# source_eagle.net
KiCad netlist of a schematic drawn in EAGLE
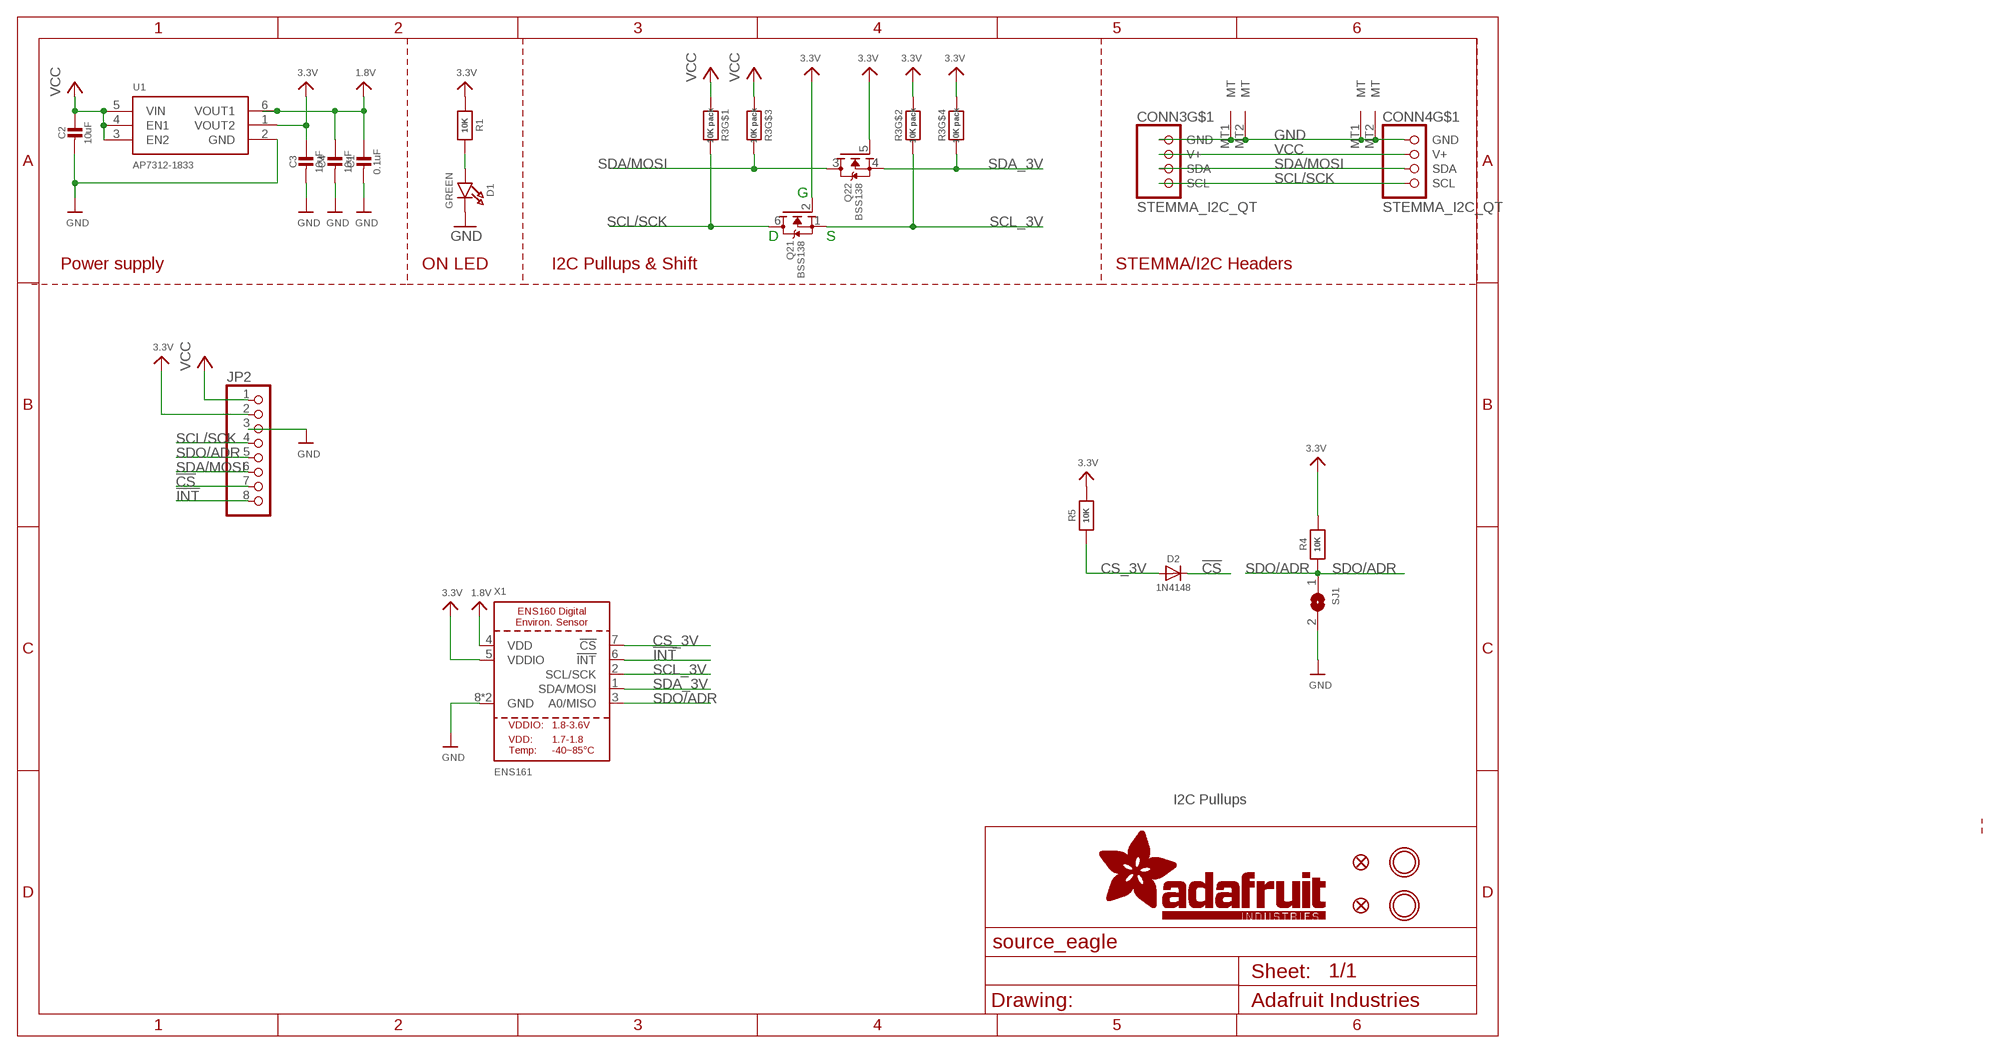
[diagram p0: schematic, sheet 1]

(export (version "E")
  (design (tool "Eeschema 10.0.6"))
  (components
    (comp (ref "C1")
      (value "0.1uF")
      (footprint "eagle-import:0603-NO")
      (libsource (lib "eagle-import") (part "CAP_CERAMIC0603_NO"))
    )
    (comp (ref "C2")
      (value "10uF")
      (footprint "eagle-import:0805-NO")
      (libsource (lib "eagle-import") (part "CAP_CERAMIC0805-NOOUTLINE"))
    )
    (comp (ref "C3")
      (value "10uF")
      (footprint "eagle-import:0805-NO")
      (libsource (lib "eagle-import") (part "CAP_CERAMIC0805-NOOUTLINE"))
    )
    (comp (ref "C4")
      (value "10uF")
      (footprint "eagle-import:0805-NO")
      (libsource (lib "eagle-import") (part "CAP_CERAMIC0805-NOOUTLINE"))
    )
    (comp (ref "CONN3")
      (value "STEMMA_I2C_QT")
      (footprint "eagle-import:JST_SH4")
      (libsource (lib "eagle-import") (part "STEMMA_I2C_QT"))
    )
    (comp (ref "CONN4")
      (value "STEMMA_I2C_QT")
      (footprint "eagle-import:JST_SH4")
      (libsource (lib "eagle-import") (part "STEMMA_I2C_QT"))
    )
    (comp (ref "D1")
      (value "GREEN")
      (footprint "eagle-import:CHIPLED_0603_NOOUTLINE")
      (libsource (lib "eagle-import") (part "LED0603_NOOUTLINE"))
    )
    (comp (ref "D2")
      (value "1N4148")
      (footprint "eagle-import:SOD-323")
      (libsource (lib "eagle-import") (part "DIODESOD-323"))
    )
    (comp (ref "FID3")
      (value "FIDUCIAL_0.5MM")
      (footprint "eagle-import:FIDUCIAL_0.5MM")
      (libsource (lib "eagle-import") (part "FIDUCIAL_0.5MM"))
    )
    (comp (ref "FID4")
      (value "FIDUCIAL_0.5MM")
      (footprint "eagle-import:FIDUCIAL_0.5MM")
      (libsource (lib "eagle-import") (part "FIDUCIAL_0.5MM"))
    )
    (comp (ref "JP2")
      (value "HEADER-1X870MIL")
      (footprint "eagle-import:1X08_ROUND_70")
      (libsource (lib "eagle-import") (part "HEADER-1X870MIL"))
    )
    (comp (ref "Q2")
      (value "BSS138")
      (footprint "eagle-import:SOT363")
      (libsource (lib "eagle-import") (part "MOSFET-N_DUAL"))
    )
    (comp (ref "R1")
      (value "10K")
      (footprint "eagle-import:0603-NO")
      (libsource (lib "eagle-import") (part "RESISTOR_0603_NOOUT"))
    )
    (comp (ref "R3")
      (value "10K pack")
      (footprint "eagle-import:RESPACK_4X0603")
      (libsource (lib "eagle-import") (part "RESISTOR_4PACK"))
    )
    (comp (ref "R4")
      (value "10K")
      (footprint "eagle-import:0603-NO")
      (libsource (lib "eagle-import") (part "RESISTOR_0603_NOOUT"))
    )
    (comp (ref "R5")
      (value "10K")
      (footprint "eagle-import:0603-NO")
      (libsource (lib "eagle-import") (part "RESISTOR_0603_NOOUT"))
    )
    (comp (ref "SJ1")
      (value "SOLDERJUMPER")
      (footprint "eagle-import:SOLDERJUMPER_ARROW_NOPASTE")
      (libsource (lib "eagle-import") (part "SOLDERJUMPER"))
    )
    (comp (ref "U$1")
      (value "MOUNTINGHOLE2.5")
      (footprint "eagle-import:MOUNTINGHOLE_2.5_PLATED")
      (libsource (lib "eagle-import") (part "MOUNTINGHOLE2.5"))
    )
    (comp (ref "U$17")
      (value "MOUNTINGHOLE2.5")
      (footprint "eagle-import:MOUNTINGHOLE_2.5_PLATED")
      (libsource (lib "eagle-import") (part "MOUNTINGHOLE2.5"))
    )
    (comp (ref "U1")
      (value "AP7312-1833")
      (footprint "eagle-import:SOT23-6")
      (libsource (lib "eagle-import") (part "VREG_SOT23-6_DUALAP7312"))
    )
    (comp (ref "X1")
      (value "ENS161")
      (footprint "eagle-import:ENS160")
      (libsource (lib "eagle-import") (part "ENS160"))
    )
  )
  (nets
    (net (code "1") (name "/CS_3V") (class "Default")
      (node (ref "D2") (pin "A") (pinfunction "A_A") (pintype "passive"))
      (node (ref "R5") (pin "1") (pinfunction "1_1") (pintype "passive"))
      (node (ref "X1") (pin "7") (pinfunction "~{CS}_7") (pintype "input"))
    )
    (net (code "2") (name "/SCL_3V") (class "Default")
      (node (ref "Q2") (pin "1") (pinfunction "S_1") (pintype "bidirectional"))
      (node (ref "R3") (pin "7") (pinfunction "2_7") (pintype "passive"))
      (node (ref "X1") (pin "2") (pinfunction "SCL/SCK_2") (pintype "input"))
    )
    (net (code "3") (name "/SCL{slash}SCK") (class "Default")
      (node (ref "CONN3") (pin "4") (pinfunction "SCL_4") (pintype "passive"))
      (node (ref "CONN4") (pin "4") (pinfunction "SCL_4") (pintype "passive"))
      (node (ref "JP2") (pin "4") (pinfunction "4_4") (pintype "passive"))
      (node (ref "Q2") (pin "6") (pinfunction "D_6") (pintype "bidirectional"))
      (node (ref "R3") (pin "8") (pinfunction "2_8") (pintype "passive"))
    )
    (net (code "4") (name "/SDA_3V") (class "Default")
      (node (ref "Q2") (pin "4") (pinfunction "S_4") (pintype "bidirectional"))
      (node (ref "R3") (pin "5") (pinfunction "2_5") (pintype "passive"))
      (node (ref "X1") (pin "1") (pinfunction "SDA/MOSI_1") (pintype "input"))
    )
    (net (code "5") (name "/SDA{slash}MOSI") (class "Default")
      (node (ref "CONN3") (pin "3") (pinfunction "SDA_3") (pintype "passive"))
      (node (ref "CONN4") (pin "3") (pinfunction "SDA_3") (pintype "passive"))
      (node (ref "JP2") (pin "6") (pinfunction "6_6") (pintype "passive"))
      (node (ref "Q2") (pin "3") (pinfunction "D_3") (pintype "bidirectional"))
      (node (ref "R3") (pin "6") (pinfunction "2_6") (pintype "passive"))
    )
    (net (code "6") (name "/SDO{slash}ADR") (class "Default")
      (node (ref "JP2") (pin "5") (pinfunction "5_5") (pintype "passive"))
      (node (ref "R4") (pin "1") (pinfunction "1_1") (pintype "passive"))
      (node (ref "SJ1") (pin "1") (pinfunction "1_1") (pintype "passive"))
      (node (ref "X1") (pin "3") (pinfunction "A0/MISO_3") (pintype "output"))
    )
    (net (code "7") (name "/~{CS}") (class "Default")
      (node (ref "D2") (pin "C") (pinfunction "C_C") (pintype "passive"))
      (node (ref "JP2") (pin "7") (pinfunction "7_7") (pintype "passive"))
    )
    (net (code "8") (name "/~{INT}") (class "Default")
      (node (ref "JP2") (pin "8") (pinfunction "8_8") (pintype "passive"))
      (node (ref "X1") (pin "6") (pinfunction "~{INT}_6") (pintype "output"))
    )
    (net (code "9") (name "1.8V") (class "Default")
      (node (ref "C1") (pin "1") (pinfunction "1_1") (pintype "passive"))
      (node (ref "C4") (pin "1") (pinfunction "1_1") (pintype "passive"))
      (node (ref "U1") (pin "6") (pinfunction "VOUT1_6") (pintype "bidirectional"))
      (node (ref "X1") (pin "4") (pinfunction "VDD_4") (pintype "power_in"))
    )
    (net (code "10") (name "3.3V") (class "Default")
      (node (ref "C3") (pin "1") (pinfunction "1_1") (pintype "passive"))
      (node (ref "JP2") (pin "2") (pinfunction "2_2") (pintype "passive"))
      (node (ref "Q2") (pin "2") (pinfunction "G_2") (pintype "bidirectional"))
      (node (ref "Q2") (pin "5") (pinfunction "G_5") (pintype "bidirectional"))
      (node (ref "R1") (pin "1") (pinfunction "1_1") (pintype "passive"))
      (node (ref "R3") (pin "2") (pinfunction "1_2") (pintype "passive"))
      (node (ref "R3") (pin "4") (pinfunction "1_4") (pintype "passive"))
      (node (ref "R4") (pin "2") (pinfunction "2_2") (pintype "passive"))
      (node (ref "R5") (pin "2") (pinfunction "2_2") (pintype "passive"))
      (node (ref "U1") (pin "1") (pinfunction "VOUT2_1") (pintype "bidirectional"))
      (node (ref "X1") (pin "5") (pinfunction "VDDIO_5") (pintype "power_in"))
    )
    (net (code "11") (name "GND") (class "Default")
      (node (ref "C1") (pin "2") (pinfunction "2_2") (pintype "passive"))
      (node (ref "C2") (pin "2") (pinfunction "2_2") (pintype "passive"))
      (node (ref "C3") (pin "2") (pinfunction "2_2") (pintype "passive"))
      (node (ref "C4") (pin "2") (pinfunction "2_2") (pintype "passive"))
      (node (ref "CONN3") (pin "1") (pinfunction "GND_1") (pintype "passive"))
      (node (ref "CONN3") (pin "MT1") (pinfunction "MT_MT1") (pintype "bidirectional"))
      (node (ref "CONN3") (pin "MT2") (pinfunction "MT_MT2") (pintype "bidirectional"))
      (node (ref "CONN4") (pin "1") (pinfunction "GND_1") (pintype "passive"))
      (node (ref "CONN4") (pin "MT1") (pinfunction "MT_MT1") (pintype "bidirectional"))
      (node (ref "CONN4") (pin "MT2") (pinfunction "MT_MT2") (pintype "bidirectional"))
      (node (ref "D1") (pin "C") (pinfunction "C_C") (pintype "passive"))
      (node (ref "JP2") (pin "3") (pinfunction "3_3") (pintype "passive"))
      (node (ref "SJ1") (pin "2") (pinfunction "2_2") (pintype "passive"))
      (node (ref "U1") (pin "2") (pinfunction "GND_2") (pintype "bidirectional"))
      (node (ref "X1") (pin "8") (pinfunction "GND_8") (pintype "power_in"))
      (node (ref "X1") (pin "9") (pinfunction "GND_9") (pintype "power_in"))
    )
    (net (code "12") (name "Net-(D1-PadA)") (class "Default")
      (node (ref "D1") (pin "A") (pinfunction "A_A") (pintype "passive"))
      (node (ref "R1") (pin "2") (pinfunction "2_2") (pintype "passive"))
    )
    (net (code "13") (name "VCC") (class "Default")
      (node (ref "C2") (pin "1") (pinfunction "1_1") (pintype "passive"))
      (node (ref "CONN3") (pin "2") (pinfunction "V+_2") (pintype "passive"))
      (node (ref "CONN4") (pin "2") (pinfunction "V+_2") (pintype "passive"))
      (node (ref "JP2") (pin "1") (pinfunction "1_1") (pintype "passive"))
      (node (ref "R3") (pin "1") (pinfunction "1_1") (pintype "passive"))
      (node (ref "R3") (pin "3") (pinfunction "1_3") (pintype "passive"))
      (node (ref "U1") (pin "3") (pinfunction "EN2_3") (pintype "bidirectional"))
      (node (ref "U1") (pin "4") (pinfunction "EN1_4") (pintype "bidirectional"))
      (node (ref "U1") (pin "5") (pinfunction "VIN_5") (pintype "bidirectional"))
    )
  )
)
